# SOC_USB_USIC.net
KiCad netlist of a schematic drawn in Altium Designer
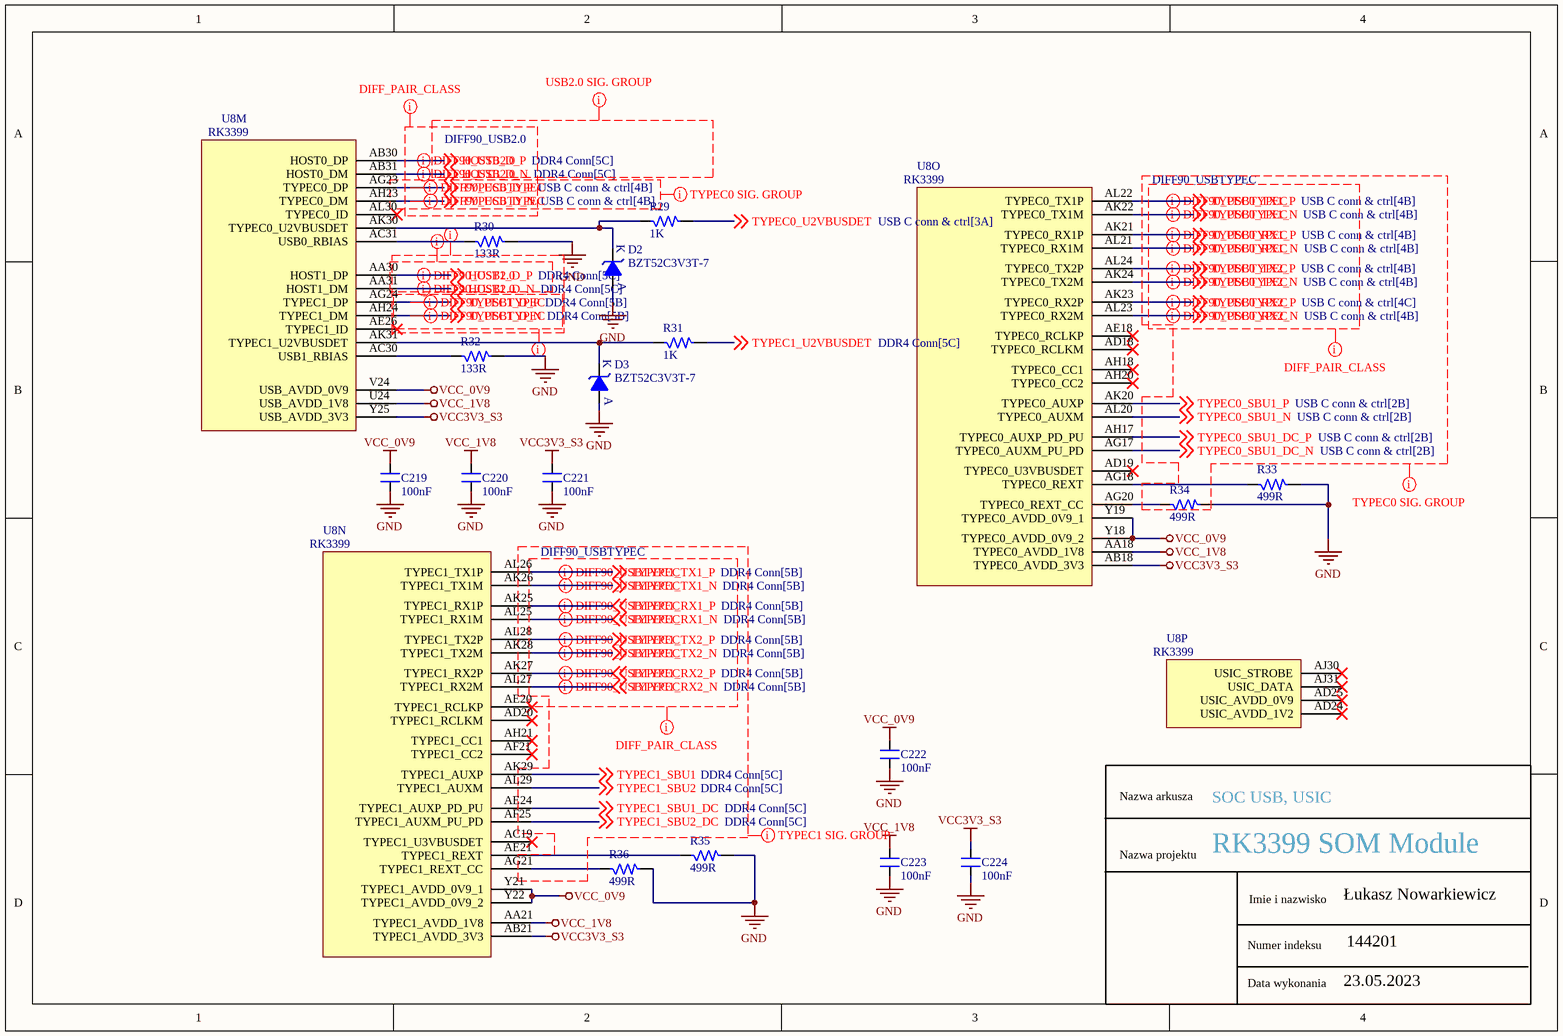
[diagram p0: SOC USB, USIC.SchDoc]

(export (version "E")
  (design (tool "Eeschema 10.0.6"))
  (components
    (comp (ref "C219")
      (value "100nF")
      (footprint "CAP_0201")
      (description "0.1µF ±10% 25V Ceramic Capacitor X5R 0201 (0603 Metric)")
      (fields
        (field (name "MANUFACTURER") "TDK Corporation")
        (field (name "MANUFACTURER PART NUMBER") "C0603X5R1E104K030BB")
      )
      (libsource (lib "RK3399 _Module_Intlib") (part "CAP_100nF-25V-10%-0201"))
    )
    (comp (ref "C220")
      (value "100nF")
      (footprint "CAP_0201")
      (description "0.1µF ±10% 25V Ceramic Capacitor X5R 0201 (0603 Metric)")
      (fields
        (field (name "MANUFACTURER") "TDK Corporation")
        (field (name "MANUFACTURER PART NUMBER") "C0603X5R1E104K030BB")
      )
      (libsource (lib "RK3399 _Module_Intlib") (part "CAP_100nF-25V-10%-0201"))
    )
    (comp (ref "C221")
      (value "100nF")
      (footprint "CAP_0201")
      (description "0.1µF ±10% 25V Ceramic Capacitor X5R 0201 (0603 Metric)")
      (fields
        (field (name "MANUFACTURER") "TDK Corporation")
        (field (name "MANUFACTURER PART NUMBER") "C0603X5R1E104K030BB")
      )
      (libsource (lib "RK3399 _Module_Intlib") (part "CAP_100nF-25V-10%-0201"))
    )
    (comp (ref "C222")
      (value "100nF")
      (footprint "CAP_0201")
      (description "0.1µF ±10% 25V Ceramic Capacitor X5R 0201 (0603 Metric)")
      (fields
        (field (name "MANUFACTURER") "TDK Corporation")
        (field (name "MANUFACTURER PART NUMBER") "C0603X5R1E104K030BB")
      )
      (libsource (lib "RK3399 _Module_Intlib") (part "CAP_100nF-25V-10%-0201"))
    )
    (comp (ref "C223")
      (value "100nF")
      (footprint "CAP_0201")
      (description "0.1µF ±10% 25V Ceramic Capacitor X5R 0201 (0603 Metric)")
      (fields
        (field (name "MANUFACTURER") "TDK Corporation")
        (field (name "MANUFACTURER PART NUMBER") "C0603X5R1E104K030BB")
      )
      (libsource (lib "RK3399 _Module_Intlib") (part "CAP_100nF-25V-10%-0201"))
    )
    (comp (ref "C224")
      (value "100nF")
      (footprint "CAP_0201")
      (description "0.1µF ±10% 25V Ceramic Capacitor X5R 0201 (0603 Metric)")
      (fields
        (field (name "MANUFACTURER") "TDK Corporation")
        (field (name "MANUFACTURER PART NUMBER") "C0603X5R1E104K030BB")
      )
      (libsource (lib "RK3399 _Module_Intlib") (part "CAP_100nF-25V-10%-0201"))
    )
    (comp (ref "D2")
      (value "BZT52C3V3T-7")
      (footprint "DIO_SOD523")
      (description "Zener Diode 3.3V 300mW ±6% Surface Mount SOD-523")
      (fields (field (name "MANUFACTURER") "Diodes Incorporated"))
      (libsource (lib "RK3399 _Module_Schlib") (part "DIO-Z_3.3V-300mW-SOD-523"))
    )
    (comp (ref "D3")
      (value "BZT52C3V3T-7")
      (footprint "DIO_SOD523")
      (description "Zener Diode 3.3V 300mW ±6% Surface Mount SOD-523")
      (fields (field (name "MANUFACTURER") "Diodes Incorporated"))
      (libsource (lib "RK3399 _Module_Schlib") (part "DIO-Z_3.3V-300mW-SOD-523"))
    )
    (comp (ref "R29")
      (value "1K")
      (footprint "RES_0201")
      (description "1 kOhms ±1% 0.05W, 1/20W Chip Resistor 0201 (0603 Metric) Thick Film")
      (fields
        (field (name "MANUFACTURER") "Yageo")
        (field (name "MANUFACTURER PART NUMBER") "RC0201FR-071KL")
      )
      (libsource (lib "RK3399 _Module_Intlib") (part "RES_1K-0.05W-1%-0201"))
    )
    (comp (ref "R30")
      (value "133R")
      (footprint "RES_0201")
      (description "133 Ohms ±1% 0.05W, 1/20W Chip Resistor 0201 (0603 Metric) Automotive AEC-Q200 Thick Film")
      (fields
        (field (name "MANUFACTURER") "Panasonic Electronic Components")
        (field (name "MANUFACTURER PART NUMBER") "ERJ-1GNF1330C")
      )
      (libsource (lib "RK3399 _Module_Intlib") (part "RES_133R-0.05W-1%-0201"))
    )
    (comp (ref "R31")
      (value "1K")
      (footprint "RES_0201")
      (description "1 kOhms ±1% 0.05W, 1/20W Chip Resistor 0201 (0603 Metric) Thick Film")
      (fields
        (field (name "MANUFACTURER") "Yageo")
        (field (name "MANUFACTURER PART NUMBER") "RC0201FR-071KL")
      )
      (libsource (lib "RK3399 _Module_Intlib") (part "RES_1K-0.05W-1%-0201"))
    )
    (comp (ref "R32")
      (value "133R")
      (footprint "RES_0201")
      (description "133 Ohms ±1% 0.05W, 1/20W Chip Resistor 0201 (0603 Metric) Automotive AEC-Q200 Thick Film")
      (fields
        (field (name "MANUFACTURER") "Panasonic Electronic Components")
        (field (name "MANUFACTURER PART NUMBER") "ERJ-1GNF1330C")
      )
      (libsource (lib "RK3399 _Module_Intlib") (part "RES_133R-0.05W-1%-0201"))
    )
    (comp (ref "R33")
      (value "499R")
      (footprint "RES_0201")
      (description "499 Ohms ±1% 0.05W, 1/20W Chip Resistor 0201 (0603 Metric) Thick Film")
      (fields
        (field (name "MANUFACTURER") "Stackpole Electronics Inc")
        (field (name "MANUFACTURER PART NUMBER") "RMCF0201FT499R")
      )
      (libsource (lib "RK3399 _Module_Intlib") (part "RES_499R-0.05W-1%-0201"))
    )
    (comp (ref "R34")
      (value "499R")
      (footprint "RES_0201")
      (description "499 Ohms ±1% 0.05W, 1/20W Chip Resistor 0201 (0603 Metric) Thick Film")
      (fields
        (field (name "MANUFACTURER") "Stackpole Electronics Inc")
        (field (name "MANUFACTURER PART NUMBER") "RMCF0201FT499R")
      )
      (libsource (lib "RK3399 _Module_Intlib") (part "RES_499R-0.05W-1%-0201"))
    )
    (comp (ref "R35")
      (value "499R")
      (footprint "RES_0201")
      (description "499 Ohms ±1% 0.05W, 1/20W Chip Resistor 0201 (0603 Metric) Thick Film")
      (fields
        (field (name "MANUFACTURER") "Stackpole Electronics Inc")
        (field (name "MANUFACTURER PART NUMBER") "RMCF0201FT499R")
      )
      (libsource (lib "RK3399 _Module_Intlib") (part "RES_499R-0.05W-1%-0201"))
    )
    (comp (ref "R36")
      (value "499R")
      (footprint "RES_0201")
      (description "499 Ohms ±1% 0.05W, 1/20W Chip Resistor 0201 (0603 Metric) Thick Film")
      (fields
        (field (name "MANUFACTURER") "Stackpole Electronics Inc")
        (field (name "MANUFACTURER PART NUMBER") "RMCF0201FT499R")
      )
      (libsource (lib "RK3399 _Module_Intlib") (part "RES_499R-0.05W-1%-0201"))
    )
    (comp (ref "U8")
      (value "RK3399")
      (footprint "FBGA828_23_826X826")
      (description "RK3399 is a low power, high performance processor for computing, personal mobile.")
      (fields (field (name "MANUFACTURER") "Rockchip"))
      (libsource (lib "EsteemPCB_SOM_Course_intlib") (part "IC_RK3399-FCBGA828"))
    )
  )
  (nets
    (net (code "1") (name "GND") (class "Default")
      (node (ref "C219") (pin "2") (pinfunction "2_2") (pintype "passive"))
      (node (ref "C220") (pin "1") (pinfunction "1_1") (pintype "passive"))
      (node (ref "C221") (pin "1") (pinfunction "1_1") (pintype "passive"))
      (node (ref "C222") (pin "1") (pinfunction "1_1") (pintype "passive"))
      (node (ref "C223") (pin "1") (pinfunction "1_1") (pintype "passive"))
      (node (ref "C224") (pin "1") (pinfunction "1_1") (pintype "passive"))
      (node (ref "D2") (pin "A") (pinfunction "A_A") (pintype "passive"))
      (node (ref "D3") (pin "A") (pinfunction "A_A") (pintype "passive"))
      (node (ref "R30") (pin "2") (pinfunction "2_2") (pintype "passive"))
      (node (ref "R32") (pin "2") (pinfunction "2_2") (pintype "passive"))
      (node (ref "R33") (pin "2") (pinfunction "2_2") (pintype "passive"))
      (node (ref "R34") (pin "2") (pinfunction "2_2") (pintype "passive"))
      (node (ref "R35") (pin "2") (pinfunction "2_2") (pintype "passive"))
      (node (ref "R36") (pin "2") (pinfunction "2_2") (pintype "passive"))
    )
    (net (code "2") (name "HOST0_D_N") (class "Default")
      (node (ref "U8") (pin "AB31") (pinfunction "HOST0_DM_AB31") (pintype "passive"))
    )
    (net (code "3") (name "HOST0_D_P") (class "Default")
      (node (ref "U8") (pin "AB30") (pinfunction "HOST0_DP_AB30") (pintype "passive"))
    )
    (net (code "4") (name "HOST1_D_N") (class "Default")
      (node (ref "U8") (pin "AA31") (pinfunction "HOST1_DM_AA31") (pintype "passive"))
    )
    (net (code "5") (name "HOST1_D_P") (class "Default")
      (node (ref "U8") (pin "AA30") (pinfunction "HOST1_DP_AA30") (pintype "passive"))
    )
    (net (code "6") (name "Net-(U8M-TYPEC0_U2VBUSDET)") (class "Default")
      (node (ref "D2") (pin "K") (pinfunction "K_K") (pintype "passive"))
      (node (ref "R29") (pin "1") (pinfunction "1_1") (pintype "passive"))
      (node (ref "U8") (pin "AK30") (pinfunction "TYPEC0_U2VBUSDET_AK30") (pintype "passive"))
    )
    (net (code "7") (name "Net-(U8M-TYPEC1_U2VBUSDET)") (class "Default")
      (node (ref "D3") (pin "K") (pinfunction "K_K") (pintype "passive"))
      (node (ref "R31") (pin "1") (pinfunction "1_1") (pintype "passive"))
      (node (ref "U8") (pin "AK31") (pinfunction "TYPEC1_U2VBUSDET_AK31") (pintype "passive"))
    )
    (net (code "8") (name "Net-(U8M-USB0_RBIAS)") (class "Default")
      (node (ref "R30") (pin "1") (pinfunction "1_1") (pintype "passive"))
      (node (ref "U8") (pin "AC31") (pinfunction "USB0_RBIAS_AC31") (pintype "passive"))
    )
    (net (code "9") (name "Net-(U8M-USB1_RBIAS)") (class "Default")
      (node (ref "R32") (pin "1") (pinfunction "1_1") (pintype "passive"))
      (node (ref "U8") (pin "AC30") (pinfunction "USB1_RBIAS_AC30") (pintype "passive"))
    )
    (net (code "10") (name "Net-(U8N-TYPEC1_REXT)") (class "Default")
      (node (ref "R35") (pin "1") (pinfunction "1_1") (pintype "passive"))
      (node (ref "U8") (pin "AE21") (pinfunction "TYPEC1_REXT_AE21") (pintype "passive"))
    )
    (net (code "11") (name "Net-(U8N-TYPEC1_REXT_CC)") (class "Default")
      (node (ref "R36") (pin "1") (pinfunction "1_1") (pintype "passive"))
      (node (ref "U8") (pin "AG21") (pinfunction "TYPEC1_REXT_CC_AG21") (pintype "passive"))
    )
    (net (code "12") (name "Net-(U8O-TYPEC0_REXT)") (class "Default")
      (node (ref "R33") (pin "1") (pinfunction "1_1") (pintype "passive"))
      (node (ref "U8") (pin "AG18") (pinfunction "TYPEC0_REXT_AG18") (pintype "passive"))
    )
    (net (code "13") (name "Net-(U8O-TYPEC0_REXT_CC)") (class "Default")
      (node (ref "R34") (pin "1") (pinfunction "1_1") (pintype "passive"))
      (node (ref "U8") (pin "AG20") (pinfunction "TYPEC0_REXT_CC_AG20") (pintype "passive"))
    )
    (net (code "14") (name "TYPEC0_D_N") (class "Default")
      (node (ref "U8") (pin "AH23") (pinfunction "TYPEC0_DM_AH23") (pintype "passive"))
    )
    (net (code "15") (name "TYPEC0_D_P") (class "Default")
      (node (ref "U8") (pin "AG23") (pinfunction "TYPEC0_DP_AG23") (pintype "passive"))
    )
    (net (code "16") (name "TYPEC0_RX1_N") (class "Default")
      (node (ref "U8") (pin "AL21") (pinfunction "TYPEC0_RX1M_AL21") (pintype "passive"))
    )
    (net (code "17") (name "TYPEC0_RX1_P") (class "Default")
      (node (ref "U8") (pin "AK21") (pinfunction "TYPEC0_RX1P_AK21") (pintype "passive"))
    )
    (net (code "18") (name "TYPEC0_RX2_N") (class "Default")
      (node (ref "U8") (pin "AL23") (pinfunction "TYPEC0_RX2M_AL23") (pintype "passive"))
    )
    (net (code "19") (name "TYPEC0_RX2_P") (class "Default")
      (node (ref "U8") (pin "AK23") (pinfunction "TYPEC0_RX2P_AK23") (pintype "passive"))
    )
    (net (code "20") (name "TYPEC0_SBU1_DC_N") (class "Default")
      (node (ref "U8") (pin "AG17") (pinfunction "TYPEC0_AUXM_PU_PD_AG17") (pintype "passive"))
    )
    (net (code "21") (name "TYPEC0_SBU1_DC_P") (class "Default")
      (node (ref "U8") (pin "AH17") (pinfunction "TYPEC0_AUXP_PD_PU_AH17") (pintype "passive"))
    )
    (net (code "22") (name "TYPEC0_SBU1_N") (class "Default")
      (node (ref "U8") (pin "AL20") (pinfunction "TYPEC0_AUXM_AL20") (pintype "passive"))
    )
    (net (code "23") (name "TYPEC0_SBU1_P") (class "Default")
      (node (ref "U8") (pin "AK20") (pinfunction "TYPEC0_AUXP_AK20") (pintype "passive"))
    )
    (net (code "24") (name "TYPEC0_TX1_N") (class "Default")
      (node (ref "U8") (pin "AK22") (pinfunction "TYPEC0_TX1M_AK22") (pintype "passive"))
    )
    (net (code "25") (name "TYPEC0_TX1_P") (class "Default")
      (node (ref "U8") (pin "AL22") (pinfunction "TYPEC0_TX1P_AL22") (pintype "passive"))
    )
    (net (code "26") (name "TYPEC0_TX2_N") (class "Default")
      (node (ref "U8") (pin "AK24") (pinfunction "TYPEC0_TX2M_AK24") (pintype "passive"))
    )
    (net (code "27") (name "TYPEC0_TX2_P") (class "Default")
      (node (ref "U8") (pin "AL24") (pinfunction "TYPEC0_TX2P_AL24") (pintype "passive"))
    )
    (net (code "28") (name "TYPEC0_U2VBUSDET") (class "Default")
      (node (ref "R29") (pin "2") (pinfunction "2_2") (pintype "passive"))
    )
    (net (code "29") (name "TYPEC1_D_N") (class "Default")
      (node (ref "U8") (pin "AH24") (pinfunction "TYPEC1_DM_AH24") (pintype "passive"))
    )
    (net (code "30") (name "TYPEC1_D_P") (class "Default")
      (node (ref "U8") (pin "AG24") (pinfunction "TYPEC1_DP_AG24") (pintype "passive"))
    )
    (net (code "31") (name "TYPEC1_RX1_N") (class "Default")
      (node (ref "U8") (pin "AL25") (pinfunction "TYPEC1_RX1M_AL25") (pintype "passive"))
    )
    (net (code "32") (name "TYPEC1_RX1_P") (class "Default")
      (node (ref "U8") (pin "AK25") (pinfunction "TYPEC1_RX1P_AK25") (pintype "passive"))
    )
    (net (code "33") (name "TYPEC1_RX2_N") (class "Default")
      (node (ref "U8") (pin "AL27") (pinfunction "TYPEC1_RX2M_AL27") (pintype "passive"))
    )
    (net (code "34") (name "TYPEC1_RX2_P") (class "Default")
      (node (ref "U8") (pin "AK27") (pinfunction "TYPEC1_RX2P_AK27") (pintype "passive"))
    )
    (net (code "35") (name "TYPEC1_SBU1") (class "Default")
      (node (ref "U8") (pin "AK29") (pinfunction "TYPEC1_AUXP_AK29") (pintype "passive"))
    )
    (net (code "36") (name "TYPEC1_SBU1_DC") (class "Default")
      (node (ref "U8") (pin "AE24") (pinfunction "TYPEC1_AUXP_PD_PU_AE24") (pintype "passive"))
    )
    (net (code "37") (name "TYPEC1_SBU2") (class "Default")
      (node (ref "U8") (pin "AL29") (pinfunction "TYPEC1_AUXM_AL29") (pintype "passive"))
    )
    (net (code "38") (name "TYPEC1_SBU2_DC") (class "Default")
      (node (ref "U8") (pin "AF25") (pinfunction "TYPEC1_AUXM_PU_PD_AF25") (pintype "passive"))
    )
    (net (code "39") (name "TYPEC1_TX1_N") (class "Default")
      (node (ref "U8") (pin "AK26") (pinfunction "TYPEC1_TX1M_AK26") (pintype "passive"))
    )
    (net (code "40") (name "TYPEC1_TX1_P") (class "Default")
      (node (ref "U8") (pin "AL26") (pinfunction "TYPEC1_TX1P_AL26") (pintype "passive"))
    )
    (net (code "41") (name "TYPEC1_TX2_N") (class "Default")
      (node (ref "U8") (pin "AK28") (pinfunction "TYPEC1_TX2M_AK28") (pintype "passive"))
    )
    (net (code "42") (name "TYPEC1_TX2_P") (class "Default")
      (node (ref "U8") (pin "AL28") (pinfunction "TYPEC1_TX2P_AL28") (pintype "passive"))
    )
    (net (code "43") (name "TYPEC1_U2VBUSDET") (class "Default")
      (node (ref "R31") (pin "2") (pinfunction "2_2") (pintype "passive"))
    )
    (net (code "44") (name "VCC3V3_S3") (class "Default")
      (node (ref "C221") (pin "2") (pinfunction "2_2") (pintype "passive"))
      (node (ref "C224") (pin "2") (pinfunction "2_2") (pintype "passive"))
      (node (ref "U8") (pin "AB18") (pinfunction "TYPEC0_AVDD_3V3_AB18") (pintype "passive"))
      (node (ref "U8") (pin "AB21") (pinfunction "TYPEC1_AVDD_3V3_AB21") (pintype "passive"))
      (node (ref "U8") (pin "Y25") (pinfunction "USB_AVDD_3V3_Y25") (pintype "passive"))
    )
    (net (code "45") (name "VCC_0V9") (class "Default")
      (node (ref "C219") (pin "1") (pinfunction "1_1") (pintype "passive"))
      (node (ref "C222") (pin "2") (pinfunction "2_2") (pintype "passive"))
      (node (ref "U8") (pin "V24") (pinfunction "USB_AVDD_0V9_V24") (pintype "passive"))
      (node (ref "U8") (pin "Y18") (pinfunction "TYPEC0_AVDD_0V9_2_Y18") (pintype "passive"))
      (node (ref "U8") (pin "Y19") (pinfunction "TYPEC0_AVDD_0V9_1_Y19") (pintype "passive"))
      (node (ref "U8") (pin "Y21") (pinfunction "TYPEC1_AVDD_0V9_1_Y21") (pintype "passive"))
      (node (ref "U8") (pin "Y22") (pinfunction "TYPEC1_AVDD_0V9_2_Y22") (pintype "passive"))
    )
    (net (code "46") (name "VCC_1V8") (class "Default")
      (node (ref "C220") (pin "2") (pinfunction "2_2") (pintype "passive"))
      (node (ref "C223") (pin "2") (pinfunction "2_2") (pintype "passive"))
      (node (ref "U8") (pin "AA18") (pinfunction "TYPEC0_AVDD_1V8_AA18") (pintype "passive"))
      (node (ref "U8") (pin "AA21") (pinfunction "TYPEC1_AVDD_1V8_AA21") (pintype "passive"))
      (node (ref "U8") (pin "U24") (pinfunction "USB_AVDD_1V8_U24") (pintype "passive"))
    )
    (net (code "47") (name "unconnected-(U8M-TYPEC0_ID-PadAL30)") (class "Default")
      (node (ref "U8") (pin "AL30") (pinfunction "TYPEC0_ID_AL30") (pintype "passive+no_connect"))
    )
    (net (code "48") (name "unconnected-(U8M-TYPEC1_ID-PadAE26)") (class "Default")
      (node (ref "U8") (pin "AE26") (pinfunction "TYPEC1_ID_AE26") (pintype "passive+no_connect"))
    )
    (net (code "49") (name "unconnected-(U8N-TYPEC1_CC1-PadAH21)") (class "Default")
      (node (ref "U8") (pin "AH21") (pinfunction "TYPEC1_CC1_AH21") (pintype "passive+no_connect"))
    )
    (net (code "50") (name "unconnected-(U8N-TYPEC1_CC2-PadAF21)") (class "Default")
      (node (ref "U8") (pin "AF21") (pinfunction "TYPEC1_CC2_AF21") (pintype "passive+no_connect"))
    )
    (net (code "51") (name "unconnected-(U8N-TYPEC1_RCLKM-PadAD20)") (class "Default")
      (node (ref "U8") (pin "AD20") (pinfunction "TYPEC1_RCLKM_AD20") (pintype "passive+no_connect"))
    )
    (net (code "52") (name "unconnected-(U8N-TYPEC1_RCLKP-PadAE20)") (class "Default")
      (node (ref "U8") (pin "AE20") (pinfunction "TYPEC1_RCLKP_AE20") (pintype "passive+no_connect"))
    )
    (net (code "53") (name "unconnected-(U8N-TYPEC1_U3VBUSDET-PadAC19)") (class "Default")
      (node (ref "U8") (pin "AC19") (pinfunction "TYPEC1_U3VBUSDET_AC19") (pintype "passive+no_connect"))
    )
    (net (code "54") (name "unconnected-(U8O-TYPEC0_CC1-PadAH18)") (class "Default")
      (node (ref "U8") (pin "AH18") (pinfunction "TYPEC0_CC1_AH18") (pintype "passive+no_connect"))
    )
    (net (code "55") (name "unconnected-(U8O-TYPEC0_CC2-PadAH20)") (class "Default")
      (node (ref "U8") (pin "AH20") (pinfunction "TYPEC0_CC2_AH20") (pintype "passive+no_connect"))
    )
    (net (code "56") (name "unconnected-(U8O-TYPEC0_RCLKM-PadAD18)") (class "Default")
      (node (ref "U8") (pin "AD18") (pinfunction "TYPEC0_RCLKM_AD18") (pintype "passive+no_connect"))
    )
    (net (code "57") (name "unconnected-(U8O-TYPEC0_RCLKP-PadAE18)") (class "Default")
      (node (ref "U8") (pin "AE18") (pinfunction "TYPEC0_RCLKP_AE18") (pintype "passive+no_connect"))
    )
    (net (code "58") (name "unconnected-(U8O-TYPEC0_U3VBUSDET-PadAD19)") (class "Default")
      (node (ref "U8") (pin "AD19") (pinfunction "TYPEC0_U3VBUSDET_AD19") (pintype "passive+no_connect"))
    )
    (net (code "59") (name "unconnected-(U8P-USIC_AVDD_0V9-PadAD25)") (class "Default")
      (node (ref "U8") (pin "AD25") (pinfunction "USIC_AVDD_0V9_AD25") (pintype "passive+no_connect"))
    )
    (net (code "60") (name "unconnected-(U8P-USIC_AVDD_1V2-PadAD24)") (class "Default")
      (node (ref "U8") (pin "AD24") (pinfunction "USIC_AVDD_1V2_AD24") (pintype "passive+no_connect"))
    )
    (net (code "61") (name "unconnected-(U8P-USIC_DATA-PadAJ31)") (class "Default")
      (node (ref "U8") (pin "AJ31") (pinfunction "USIC_DATA_AJ31") (pintype "passive+no_connect"))
    )
    (net (code "62") (name "unconnected-(U8P-USIC_STROBE-PadAJ30)") (class "Default")
      (node (ref "U8") (pin "AJ30") (pinfunction "USIC_STROBE_AJ30") (pintype "passive+no_connect"))
    )
  )
)
